# nintendac.net
KiCad netlist of a schematic drawn in EAGLE
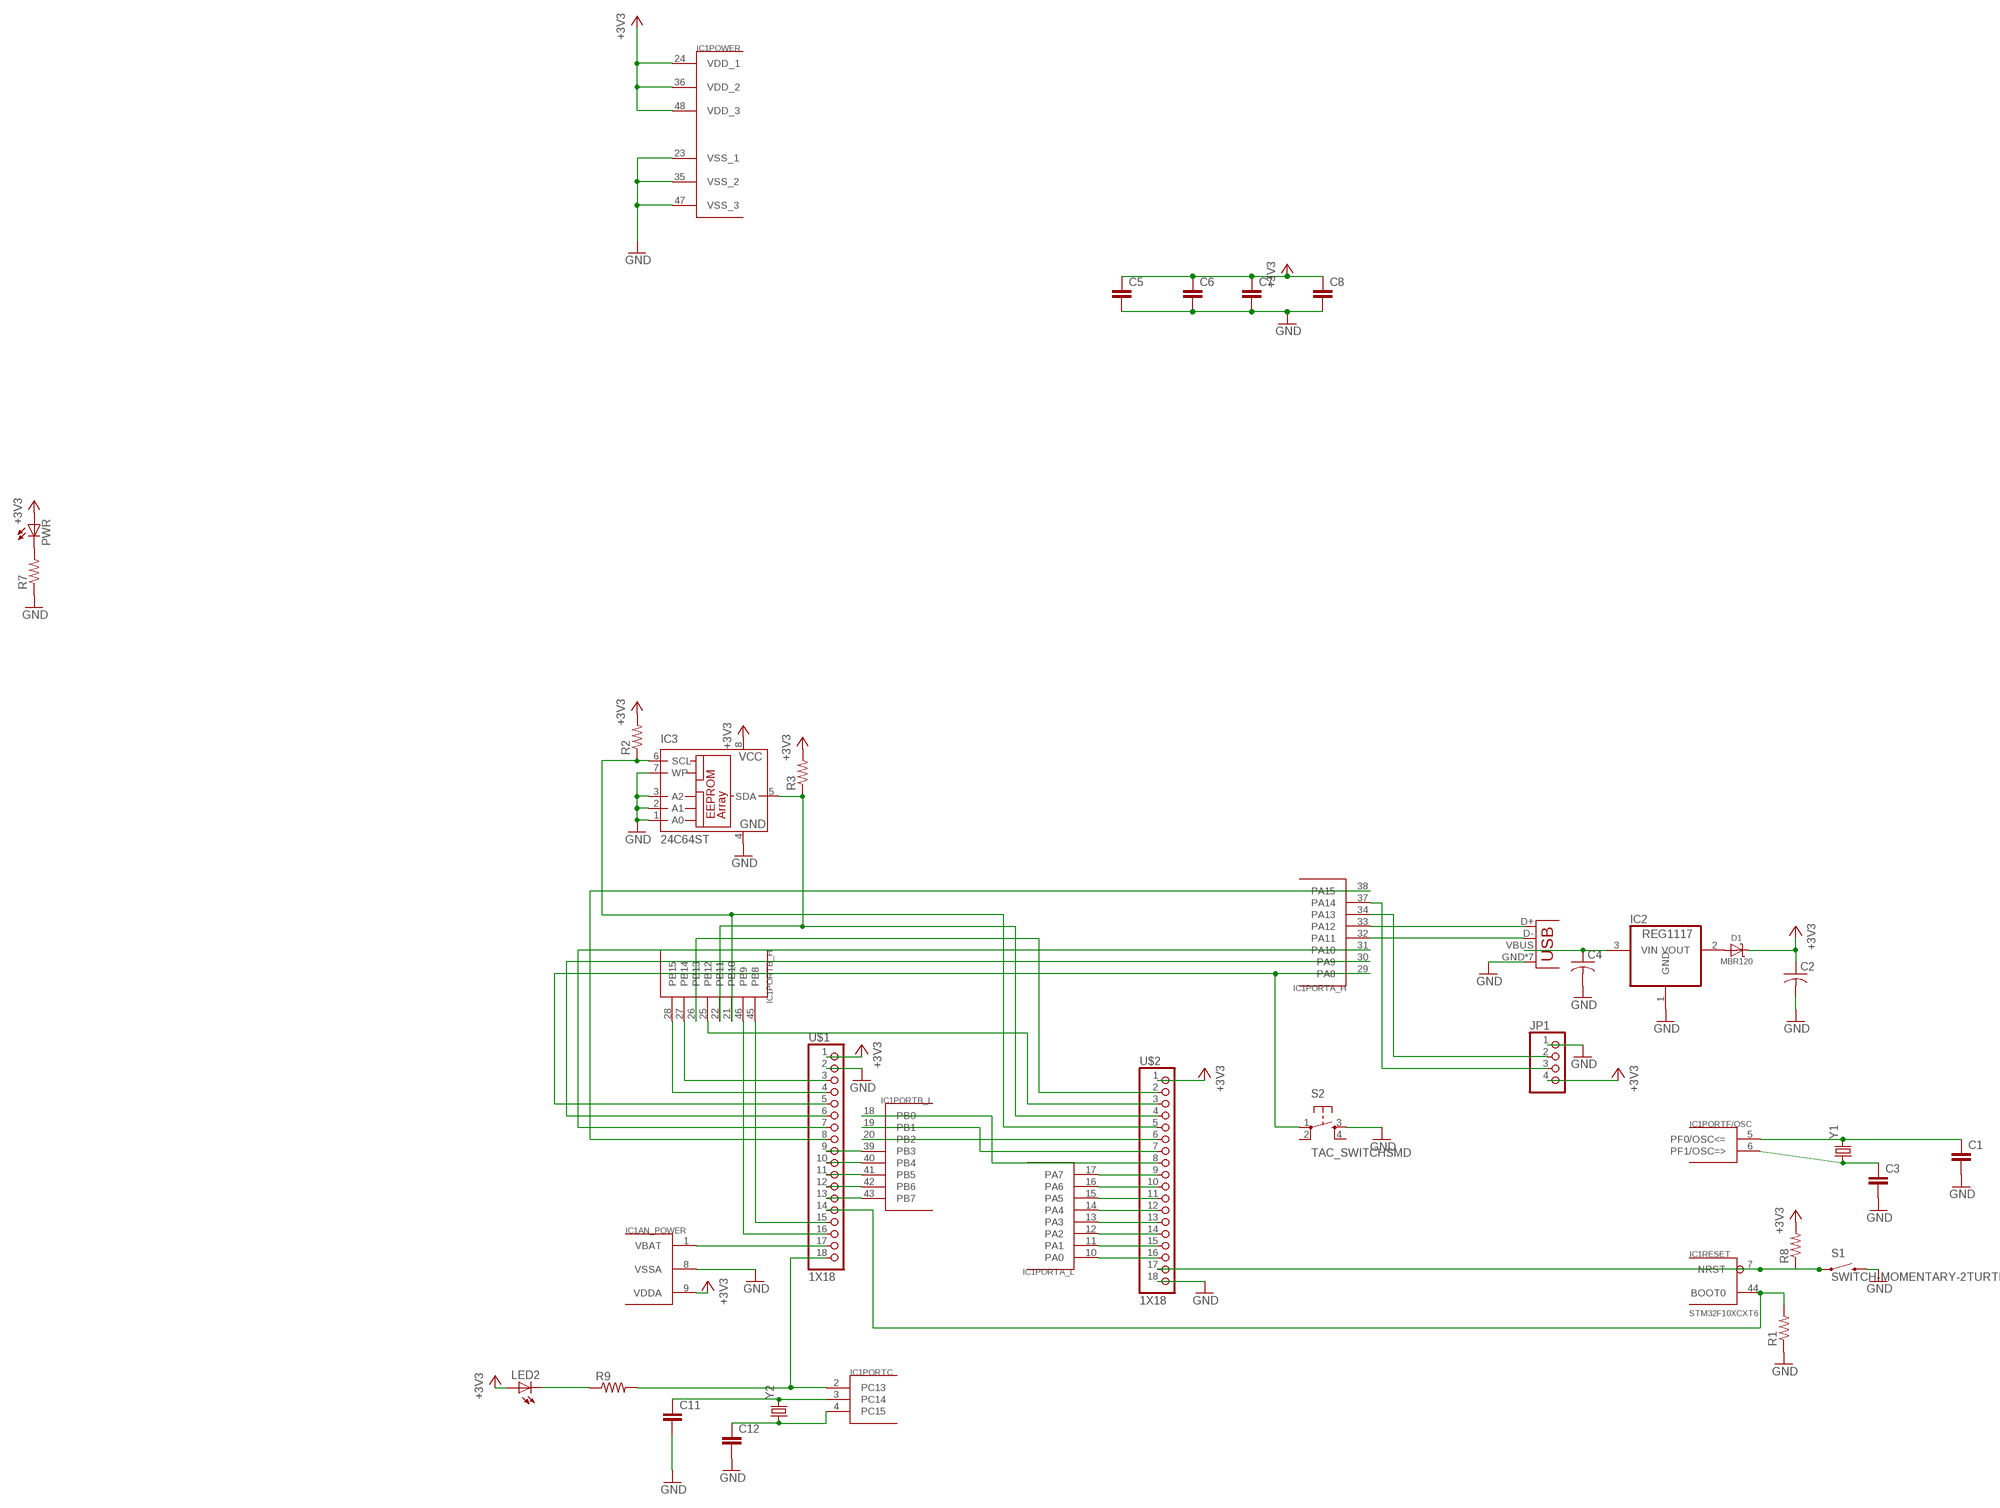
[diagram p0: schematic, sheet 1]

(export (version "E")
  (design (tool "Eeschema 10.0.6"))
  (components
    (comp (ref "C1")
      (value "CAP0805")
      (footprint "eagle-import:0805")
      (libsource (lib "eagle-import") (part "CAP0805"))
    )
    (comp (ref "C2")
      (value "C-USC1210")
      (footprint "eagle-import:C1210")
      (libsource (lib "eagle-import") (part "C-USC1210"))
    )
    (comp (ref "C3")
      (value "CAP0805")
      (footprint "eagle-import:0805")
      (libsource (lib "eagle-import") (part "CAP0805"))
    )
    (comp (ref "C4")
      (value "C-USC1210")
      (footprint "eagle-import:C1210")
      (libsource (lib "eagle-import") (part "C-USC1210"))
    )
    (comp (ref "C5")
      (value "CAP0805")
      (footprint "eagle-import:0805")
      (libsource (lib "eagle-import") (part "CAP0805"))
    )
    (comp (ref "C6")
      (value "CAP0805")
      (footprint "eagle-import:0805")
      (libsource (lib "eagle-import") (part "CAP0805"))
    )
    (comp (ref "C7")
      (value "CAP0805")
      (footprint "eagle-import:0805")
      (libsource (lib "eagle-import") (part "CAP0805"))
    )
    (comp (ref "C8")
      (value "CAP0805")
      (footprint "eagle-import:0805")
      (libsource (lib "eagle-import") (part "CAP0805"))
    )
    (comp (ref "C11")
      (value "CAP0805")
      (footprint "eagle-import:0805")
      (libsource (lib "eagle-import") (part "CAP0805"))
    )
    (comp (ref "C12")
      (value "CAP0805")
      (footprint "eagle-import:0805")
      (libsource (lib "eagle-import") (part "CAP0805"))
    )
    (comp (ref "D1")
      (value "MBR120")
      (footprint "eagle-import:SOD-123")
      (libsource (lib "eagle-import") (part "DIODE-SCHOTTKYSOD-123"))
    )
    (comp (ref "IC1")
      (value "STM32F10XCXT6")
      (footprint "eagle-import:TQFP48")
      (libsource (lib "eagle-import") (part "STM32F10XCXT6"))
    )
    (comp (ref "IC2")
      (value "REG1117")
      (footprint "eagle-import:SOT223")
      (libsource (lib "eagle-import") (part "REG1117"))
    )
    (comp (ref "IC3")
      (value "24C64ST")
      (footprint "eagle-import:TSSOP8")
      (fields (field (name "MPN") "CAT24C64YI-GT3"))
      (libsource (lib "eagle-import") (part "24STC64"))
    )
    (comp (ref "JP1")
      (value "PINHD-1X4")
      (footprint "eagle-import:1X04")
      (libsource (lib "eagle-import") (part "PINHD-1X4"))
    )
    (comp (ref "LED2")
      (value "LEDCHIP-LED0805")
      (footprint "eagle-import:CHIP-LED0805")
      (libsource (lib "eagle-import") (part "LEDCHIP-LED0805"))
    )
    (comp (ref "PWR")
      (value "LEDCHIP-LED0805")
      (footprint "eagle-import:CHIP-LED0805")
      (libsource (lib "eagle-import") (part "LEDCHIP-LED0805"))
    )
    (comp (ref "R1")
      (value "RESISTOR0805-RES")
      (footprint "eagle-import:0805")
      (libsource (lib "eagle-import") (part "RESISTOR0805-RES"))
    )
    (comp (ref "R2")
      (value "RESISTOR0805-RES")
      (footprint "eagle-import:0805")
      (libsource (lib "eagle-import") (part "RESISTOR0805-RES"))
    )
    (comp (ref "R3")
      (value "RESISTOR0805-RES")
      (footprint "eagle-import:0805")
      (libsource (lib "eagle-import") (part "RESISTOR0805-RES"))
    )
    (comp (ref "R7")
      (value "RESISTOR0805-RES")
      (footprint "eagle-import:0805")
      (libsource (lib "eagle-import") (part "RESISTOR0805-RES"))
    )
    (comp (ref "R8")
      (value "RESISTOR0805-RES")
      (footprint "eagle-import:0805")
      (libsource (lib "eagle-import") (part "RESISTOR0805-RES"))
    )
    (comp (ref "R9")
      (value "RESISTOR0805-RES")
      (footprint "eagle-import:0805")
      (libsource (lib "eagle-import") (part "RESISTOR0805-RES"))
    )
    (comp (ref "S1")
      (value "SWITCH-MOMENTARY-2TURTLE")
      (footprint "eagle-import:KMR2")
      (libsource (lib "eagle-import") (part "SWITCH-MOMENTARY-2TURTLE"))
    )
    (comp (ref "S2")
      (value "TAC_SWITCHSMD")
      (footprint "eagle-import:TACTILE-SWITCH-SMD")
      (libsource (lib "eagle-import") (part "TAC_SWITCHSMD"))
    )
    (comp (ref "U$1")
      (value "1X18")
      (footprint "eagle-import:1X18")
      (libsource (lib "eagle-import") (part "1X18"))
    )
    (comp (ref "U$2")
      (value "1X18")
      (footprint "eagle-import:1X18")
      (libsource (lib "eagle-import") (part "1X18"))
    )
    (comp (ref "X1")
      (value "USB-MICROB")
      (footprint "eagle-import:USB-MICROB")
      (libsource (lib "eagle-import") (part "USB-MICROB"))
    )
    (comp (ref "Y1")
      (value "CRYSTALHC49US")
      (footprint "eagle-import:HC49US")
      (libsource (lib "eagle-import") (part "CRYSTALHC49US"))
    )
    (comp (ref "Y2")
      (value "CRYSTALTC26H_EZ")
      (footprint "eagle-import:TC26HEZ")
      (libsource (lib "eagle-import") (part "CRYSTALTC26H_EZ"))
    )
  )
  (nets
    (net (code "1") (name "+3V3") (class "Default")
      (node (ref "C2") (pin "1") (pinfunction "1_1") (pintype "passive"))
      (node (ref "C5") (pin "1") (pinfunction "1_1") (pintype "passive"))
      (node (ref "C6") (pin "1") (pinfunction "1_1") (pintype "passive"))
      (node (ref "C7") (pin "1") (pinfunction "1_1") (pintype "passive"))
      (node (ref "C8") (pin "1") (pinfunction "1_1") (pintype "passive"))
      (node (ref "D1") (pin "C") (pinfunction "C_C") (pintype "passive"))
      (node (ref "IC1") (pin "24") (pinfunction "VDD_1_24") (pintype "power_in"))
      (node (ref "IC1") (pin "36") (pinfunction "VDD_2_36") (pintype "power_in"))
      (node (ref "IC1") (pin "48") (pinfunction "VDD_3_48") (pintype "power_in"))
      (node (ref "IC1") (pin "9") (pinfunction "VDDA_9") (pintype "power_in"))
      (node (ref "IC3") (pin "8") (pinfunction "VCC_8") (pintype "power_in"))
      (node (ref "JP1") (pin "4") (pinfunction "4_4") (pintype "passive"))
      (node (ref "LED2") (pin "A") (pinfunction "A_A") (pintype "passive"))
      (node (ref "PWR") (pin "A") (pinfunction "A_A") (pintype "passive"))
      (node (ref "R2") (pin "2") (pinfunction "2_2") (pintype "passive"))
      (node (ref "R3") (pin "2") (pinfunction "2_2") (pintype "passive"))
      (node (ref "R8") (pin "2") (pinfunction "2_2") (pintype "passive"))
      (node (ref "U$1") (pin "1") (pinfunction "1_1") (pintype "passive"))
      (node (ref "U$2") (pin "1") (pinfunction "1_1") (pintype "passive"))
    )
    (net (code "2") (name "GND") (class "Default")
      (node (ref "C1") (pin "2") (pinfunction "2_2") (pintype "passive"))
      (node (ref "C11") (pin "2") (pinfunction "2_2") (pintype "passive"))
      (node (ref "C12") (pin "2") (pinfunction "2_2") (pintype "passive"))
      (node (ref "C2") (pin "2") (pinfunction "2_2") (pintype "passive"))
      (node (ref "C3") (pin "2") (pinfunction "2_2") (pintype "passive"))
      (node (ref "C4") (pin "2") (pinfunction "2_2") (pintype "passive"))
      (node (ref "C5") (pin "2") (pinfunction "2_2") (pintype "passive"))
      (node (ref "C6") (pin "2") (pinfunction "2_2") (pintype "passive"))
      (node (ref "C7") (pin "2") (pinfunction "2_2") (pintype "passive"))
      (node (ref "C8") (pin "2") (pinfunction "2_2") (pintype "passive"))
      (node (ref "IC1") (pin "23") (pinfunction "VSS_1_23") (pintype "power_in"))
      (node (ref "IC1") (pin "35") (pinfunction "VSS_2_35") (pintype "power_in"))
      (node (ref "IC1") (pin "47") (pinfunction "VSS_3_47") (pintype "power_in"))
      (node (ref "IC1") (pin "8") (pinfunction "VSSA_8") (pintype "power_in"))
      (node (ref "IC2") (pin "1") (pinfunction "GND_1") (pintype "power_in"))
      (node (ref "IC3") (pin "1") (pinfunction "A0_1") (pintype "input"))
      (node (ref "IC3") (pin "2") (pinfunction "A1_2") (pintype "input"))
      (node (ref "IC3") (pin "3") (pinfunction "A2_3") (pintype "input"))
      (node (ref "IC3") (pin "4") (pinfunction "GND_4") (pintype "power_in"))
      (node (ref "IC3") (pin "7") (pinfunction "WP_7") (pintype "input"))
      (node (ref "JP1") (pin "1") (pinfunction "1_1") (pintype "passive"))
      (node (ref "R1") (pin "1") (pinfunction "1_1") (pintype "passive"))
      (node (ref "R7") (pin "1") (pinfunction "1_1") (pintype "passive"))
      (node (ref "S1") (pin "3") (pinfunction "2_3") (pintype "passive"))
      (node (ref "S2") (pin "3") (pinfunction "3_3") (pintype "passive"))
      (node (ref "U$1") (pin "2") (pinfunction "2_2") (pintype "passive"))
      (node (ref "U$2") (pin "18") (pinfunction "18_18") (pintype "passive"))
      (node (ref "X1") (pin "GND") (pinfunction "GND_GND") (pintype "bidirectional"))
      (node (ref "X1") (pin "P1") (pinfunction "GND_P1") (pintype "bidirectional"))
      (node (ref "X1") (pin "P2") (pinfunction "GND_P2") (pintype "bidirectional"))
      (node (ref "X1") (pin "P3") (pinfunction "GND_P3") (pintype "bidirectional"))
      (node (ref "X1") (pin "P4") (pinfunction "GND_P4") (pintype "bidirectional"))
      (node (ref "X1") (pin "P5") (pinfunction "GND_P5") (pintype "bidirectional"))
      (node (ref "X1") (pin "P6") (pinfunction "GND_P6") (pintype "bidirectional"))
    )
    (net (code "3") (name "Net-(IC1A-VBAT)") (class "Default")
      (node (ref "IC1") (pin "1") (pinfunction "VBAT_1") (pintype "power_in"))
      (node (ref "U$1") (pin "17") (pinfunction "17_17") (pintype "passive"))
    )
    (net (code "4") (name "Net-(IC1B-PA8)") (class "Default")
      (node (ref "IC1") (pin "29") (pinfunction "PA8_29") (pintype "bidirectional"))
      (node (ref "S2") (pin "1") (pinfunction "1_1") (pintype "passive"))
      (node (ref "U$1") (pin "5") (pinfunction "5_5") (pintype "passive"))
    )
    (net (code "5") (name "Net-(IC1B-PA9)") (class "Default")
      (node (ref "IC1") (pin "30") (pinfunction "PA9_30") (pintype "bidirectional"))
      (node (ref "U$1") (pin "6") (pinfunction "6_6") (pintype "passive"))
    )
    (net (code "6") (name "Net-(IC1B-PA10)") (class "Default")
      (node (ref "IC1") (pin "31") (pinfunction "PA10_31") (pintype "bidirectional"))
      (node (ref "U$1") (pin "7") (pinfunction "7_7") (pintype "passive"))
    )
    (net (code "7") (name "Net-(IC1B-PA11)") (class "Default")
      (node (ref "IC1") (pin "32") (pinfunction "PA11_32") (pintype "bidirectional"))
      (node (ref "X1") (pin "D-") (pinfunction "D-_D-") (pintype "bidirectional"))
    )
    (net (code "8") (name "Net-(IC1B-PA12)") (class "Default")
      (node (ref "IC1") (pin "33") (pinfunction "PA12_33") (pintype "bidirectional"))
      (node (ref "X1") (pin "D+") (pinfunction "D+_D+") (pintype "bidirectional"))
    )
    (net (code "9") (name "Net-(IC1B-PA13)") (class "Default")
      (node (ref "IC1") (pin "34") (pinfunction "PA13_34") (pintype "bidirectional"))
      (node (ref "JP1") (pin "2") (pinfunction "2_2") (pintype "passive"))
    )
    (net (code "10") (name "Net-(IC1B-PA14)") (class "Default")
      (node (ref "IC1") (pin "37") (pinfunction "PA14_37") (pintype "bidirectional"))
      (node (ref "JP1") (pin "3") (pinfunction "3_3") (pintype "passive"))
    )
    (net (code "11") (name "Net-(IC1B-PA15)") (class "Default")
      (node (ref "IC1") (pin "38") (pinfunction "PA15_38") (pintype "bidirectional"))
      (node (ref "U$1") (pin "8") (pinfunction "8_8") (pintype "passive"))
    )
    (net (code "12") (name "Net-(IC1C-PA0)") (class "Default")
      (node (ref "IC1") (pin "10") (pinfunction "PA0_10") (pintype "bidirectional"))
      (node (ref "U$2") (pin "16") (pinfunction "16_16") (pintype "passive"))
    )
    (net (code "13") (name "Net-(IC1C-PA1)") (class "Default")
      (node (ref "IC1") (pin "11") (pinfunction "PA1_11") (pintype "bidirectional"))
      (node (ref "U$2") (pin "15") (pinfunction "15_15") (pintype "passive"))
    )
    (net (code "14") (name "Net-(IC1C-PA2)") (class "Default")
      (node (ref "IC1") (pin "12") (pinfunction "PA2_12") (pintype "bidirectional"))
      (node (ref "U$2") (pin "14") (pinfunction "14_14") (pintype "passive"))
    )
    (net (code "15") (name "Net-(IC1C-PA3)") (class "Default")
      (node (ref "IC1") (pin "13") (pinfunction "PA3_13") (pintype "bidirectional"))
      (node (ref "U$2") (pin "13") (pinfunction "13_13") (pintype "passive"))
    )
    (net (code "16") (name "Net-(IC1C-PA4)") (class "Default")
      (node (ref "IC1") (pin "14") (pinfunction "PA4_14") (pintype "bidirectional"))
      (node (ref "U$2") (pin "12") (pinfunction "12_12") (pintype "passive"))
    )
    (net (code "17") (name "Net-(IC1C-PA5)") (class "Default")
      (node (ref "IC1") (pin "15") (pinfunction "PA5_15") (pintype "bidirectional"))
      (node (ref "U$2") (pin "11") (pinfunction "11_11") (pintype "passive"))
    )
    (net (code "18") (name "Net-(IC1C-PA6)") (class "Default")
      (node (ref "IC1") (pin "16") (pinfunction "PA6_16") (pintype "bidirectional"))
      (node (ref "U$2") (pin "10") (pinfunction "10_10") (pintype "passive"))
    )
    (net (code "19") (name "Net-(IC1C-PA7)") (class "Default")
      (node (ref "IC1") (pin "17") (pinfunction "PA7_17") (pintype "bidirectional"))
      (node (ref "U$2") (pin "9") (pinfunction "9_9") (pintype "passive"))
    )
    (net (code "20") (name "Net-(IC1D-PB8)") (class "Default")
      (node (ref "IC1") (pin "45") (pinfunction "PB8_45") (pintype "bidirectional"))
      (node (ref "U$1") (pin "15") (pinfunction "15_15") (pintype "passive"))
    )
    (net (code "21") (name "Net-(IC1D-PB9)") (class "Default")
      (node (ref "IC1") (pin "46") (pinfunction "PB9_46") (pintype "bidirectional"))
      (node (ref "U$1") (pin "16") (pinfunction "16_16") (pintype "passive"))
    )
    (net (code "22") (name "Net-(IC1D-PB10)") (class "Default")
      (node (ref "IC1") (pin "21") (pinfunction "PB10_21") (pintype "bidirectional"))
      (node (ref "IC3") (pin "6") (pinfunction "SCL_6") (pintype "input"))
      (node (ref "R2") (pin "1") (pinfunction "1_1") (pintype "passive"))
      (node (ref "U$2") (pin "5") (pinfunction "5_5") (pintype "passive"))
    )
    (net (code "23") (name "Net-(IC1D-PB11)") (class "Default")
      (node (ref "IC1") (pin "22") (pinfunction "PB11_22") (pintype "bidirectional"))
      (node (ref "IC3") (pin "5") (pinfunction "SDA_5") (pintype "bidirectional"))
      (node (ref "R3") (pin "1") (pinfunction "1_1") (pintype "passive"))
      (node (ref "U$2") (pin "4") (pinfunction "4_4") (pintype "passive"))
    )
    (net (code "24") (name "Net-(IC1D-PB12)") (class "Default")
      (node (ref "IC1") (pin "25") (pinfunction "PB12_25") (pintype "bidirectional"))
      (node (ref "U$2") (pin "3") (pinfunction "3_3") (pintype "passive"))
    )
    (net (code "25") (name "Net-(IC1D-PB13)") (class "Default")
      (node (ref "IC1") (pin "26") (pinfunction "PB13_26") (pintype "bidirectional"))
      (node (ref "U$2") (pin "2") (pinfunction "2_2") (pintype "passive"))
    )
    (net (code "26") (name "Net-(IC1D-PB14)") (class "Default")
      (node (ref "IC1") (pin "27") (pinfunction "PB14_27") (pintype "bidirectional"))
      (node (ref "U$1") (pin "3") (pinfunction "3_3") (pintype "passive"))
    )
    (net (code "27") (name "Net-(IC1D-PB15)") (class "Default")
      (node (ref "IC1") (pin "28") (pinfunction "PB15_28") (pintype "bidirectional"))
      (node (ref "U$1") (pin "4") (pinfunction "4_4") (pintype "passive"))
    )
    (net (code "28") (name "Net-(IC1E-PB0)") (class "Default")
      (node (ref "IC1") (pin "18") (pinfunction "PB0_18") (pintype "bidirectional"))
      (node (ref "U$2") (pin "8") (pinfunction "8_8") (pintype "passive"))
    )
    (net (code "29") (name "Net-(IC1E-PB1)") (class "Default")
      (node (ref "IC1") (pin "19") (pinfunction "PB1_19") (pintype "bidirectional"))
      (node (ref "U$2") (pin "7") (pinfunction "7_7") (pintype "passive"))
    )
    (net (code "30") (name "Net-(IC1E-PB2)") (class "Default")
      (node (ref "IC1") (pin "20") (pinfunction "PB2_20") (pintype "bidirectional"))
      (node (ref "U$2") (pin "6") (pinfunction "6_6") (pintype "passive"))
    )
    (net (code "31") (name "Net-(IC1E-PB3)") (class "Default")
      (node (ref "IC1") (pin "39") (pinfunction "PB3_39") (pintype "bidirectional"))
      (node (ref "U$1") (pin "9") (pinfunction "9_9") (pintype "passive"))
    )
    (net (code "32") (name "Net-(IC1E-PB4)") (class "Default")
      (node (ref "IC1") (pin "40") (pinfunction "PB4_40") (pintype "bidirectional"))
      (node (ref "U$1") (pin "10") (pinfunction "10_10") (pintype "passive"))
    )
    (net (code "33") (name "Net-(IC1E-PB5)") (class "Default")
      (node (ref "IC1") (pin "41") (pinfunction "PB5_41") (pintype "bidirectional"))
      (node (ref "U$1") (pin "11") (pinfunction "11_11") (pintype "passive"))
    )
    (net (code "34") (name "Net-(IC1E-PB6)") (class "Default")
      (node (ref "IC1") (pin "42") (pinfunction "PB6_42") (pintype "bidirectional"))
      (node (ref "U$1") (pin "12") (pinfunction "12_12") (pintype "passive"))
    )
    (net (code "35") (name "Net-(IC1E-PB7)") (class "Default")
      (node (ref "IC1") (pin "43") (pinfunction "PB7_43") (pintype "bidirectional"))
      (node (ref "U$1") (pin "13") (pinfunction "13_13") (pintype "passive"))
    )
    (net (code "36") (name "Net-(IC1F-PC13)") (class "Default")
      (node (ref "IC1") (pin "2") (pinfunction "PC13_2") (pintype "bidirectional"))
      (node (ref "R9") (pin "2") (pinfunction "2_2") (pintype "passive"))
      (node (ref "U$1") (pin "18") (pinfunction "18_18") (pintype "passive"))
    )
    (net (code "37") (name "Net-(IC1F-PC14)") (class "Default")
      (node (ref "C11") (pin "1") (pinfunction "1_1") (pintype "passive"))
      (node (ref "IC1") (pin "3") (pinfunction "PC14_3") (pintype "bidirectional"))
      (node (ref "Y2") (pin "2") (pinfunction "2_2") (pintype "passive"))
    )
    (net (code "38") (name "Net-(IC1F-PC15)") (class "Default")
      (node (ref "C12") (pin "1") (pinfunction "1_1") (pintype "passive"))
      (node (ref "IC1") (pin "4") (pinfunction "PC15_4") (pintype "bidirectional"))
      (node (ref "Y2") (pin "1") (pinfunction "1_1") (pintype "passive"))
    )
    (net (code "39") (name "Net-(IC1G-PF0{slash}OSC<=)") (class "Default")
      (node (ref "C1") (pin "1") (pinfunction "1_1") (pintype "passive"))
      (node (ref "IC1") (pin "5") (pinfunction "PF0/OSC<=_5") (pintype "bidirectional"))
      (node (ref "Y1") (pin "2") (pinfunction "2_2") (pintype "passive"))
    )
    (net (code "40") (name "Net-(IC1G-PF1{slash}OSC=>)") (class "Default")
      (node (ref "C3") (pin "1") (pinfunction "1_1") (pintype "passive"))
      (node (ref "IC1") (pin "6") (pinfunction "PF1/OSC=>_6") (pintype "bidirectional"))
      (node (ref "Y1") (pin "1") (pinfunction "1_1") (pintype "passive"))
    )
    (net (code "41") (name "Net-(IC1I-BOOT0)") (class "Default")
      (node (ref "IC1") (pin "44") (pinfunction "BOOT0_44") (pintype "input"))
      (node (ref "R1") (pin "2") (pinfunction "2_2") (pintype "passive"))
      (node (ref "U$1") (pin "14") (pinfunction "14_14") (pintype "passive"))
    )
    (net (code "42") (name "Net-(IC1I-NRST)") (class "Default")
      (node (ref "IC1") (pin "7") (pinfunction "NRST_7") (pintype "input"))
      (node (ref "R8") (pin "1") (pinfunction "1_1") (pintype "passive"))
      (node (ref "S1") (pin "1") (pinfunction "1_1") (pintype "passive"))
      (node (ref "U$2") (pin "17") (pinfunction "17_17") (pintype "passive"))
    )
    (net (code "43") (name "Net-(IC2-VIN)") (class "Default")
      (node (ref "C4") (pin "1") (pinfunction "1_1") (pintype "passive"))
      (node (ref "IC2") (pin "3") (pinfunction "VIN_3") (pintype "input"))
      (node (ref "X1") (pin "VBUS") (pinfunction "VBUS_VBUS") (pintype "bidirectional"))
    )
    (net (code "44") (name "Net-(IC2-VOUT)") (class "Default")
      (node (ref "D1") (pin "A") (pinfunction "A_A") (pintype "passive"))
      (node (ref "IC2") (pin "2") (pinfunction "VOUT_2") (pintype "output"))
    )
    (net (code "45") (name "Net-(LED2-PadC)") (class "Default")
      (node (ref "LED2") (pin "C") (pinfunction "C_C") (pintype "passive"))
      (node (ref "R9") (pin "1") (pinfunction "1_1") (pintype "passive"))
    )
    (net (code "46") (name "Net-(PWR-PadC)") (class "Default")
      (node (ref "PWR") (pin "C") (pinfunction "C_C") (pintype "passive"))
      (node (ref "R7") (pin "2") (pinfunction "2_2") (pintype "passive"))
    )
    (net (code "47") (name "unconnected-(S2-Pad2)") (class "Default")
      (node (ref "S2") (pin "2") (pinfunction "2_2") (pintype "passive"))
    )
    (net (code "48") (name "unconnected-(S2-Pad4)") (class "Default")
      (node (ref "S2") (pin "4") (pinfunction "4_4") (pintype "passive"))
    )
  )
)
